# Rpi_Connections.net
KiCad netlist of a schematic drawn in Altium Designer
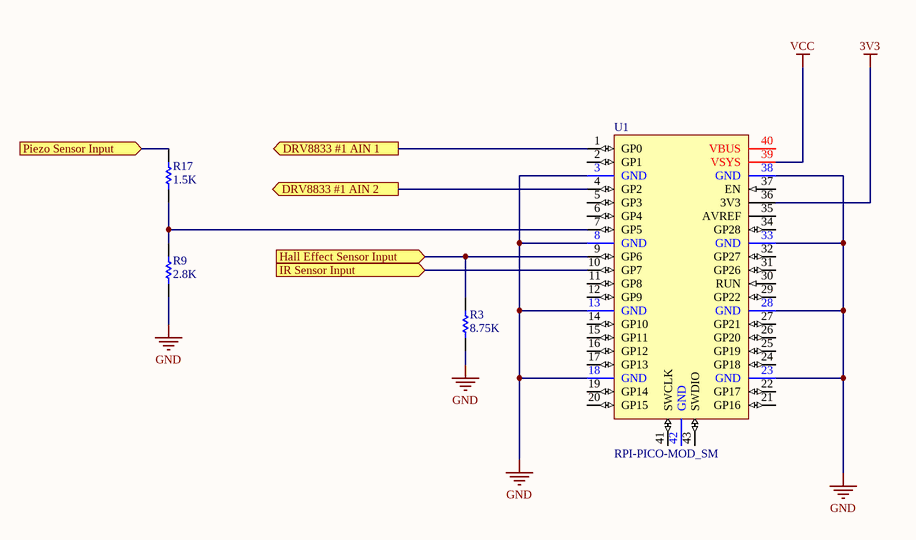
[diagram p0: Rpi Connections.SchDoc]

(export (version "E")
  (design (tool "Eeschema 10.0.6"))
  (components
    (comp (ref "R3")
      (value "8.75K")
      (description "Resistor")
      (libsource (lib "Simulation Generic Components") (part "Resistor"))
    )
    (comp (ref "R9")
      (value "2.8K")
      (description "Resistor")
      (libsource (lib "Simulation Generic Components") (part "Resistor"))
    )
    (comp (ref "R17")
      (value "1.5K")
      (description "Resistor")
      (libsource (lib "Simulation Generic Components") (part "Resistor"))
    )
    (comp (ref "U1")
      (value "RPI-PICO-MOD_SM")
      (footprint "AG.Modules:RPI-PICO-MOD")
      (description "RASPBERRY PI PICO RP2040 BOARD NO TEST PADS")
      (fields
        (field (name "MANUFACTURER") "Raspberry Pi Foundation")
        (field (name "MANUFACTURER PART NO") "SC0915")
      )
      (libsource (lib "RPi_Pico") (part "RPI-PICO-MOD_SM"))
    )
  )
  (nets
    (net (code "1") (name "/DRV8833 #1 AIN 1") (class "Default")
      (node (ref "U1") (pin "1") (pinfunction "GP0_1") (pintype "bidirectional"))
    )
    (net (code "2") (name "/DRV8833 #1 AIN 2") (class "Default")
      (node (ref "U1") (pin "4") (pinfunction "GP2_4") (pintype "bidirectional"))
    )
    (net (code "3") (name "/Hall Effect Sensor Input") (class "Default")
      (node (ref "R3") (pin "2") (pinfunction "2_2") (pintype "passive"))
      (node (ref "U1") (pin "9") (pinfunction "GP6_9") (pintype "bidirectional"))
    )
    (net (code "4") (name "/IR Sensor Input") (class "Default")
      (node (ref "U1") (pin "10") (pinfunction "GP7_10") (pintype "bidirectional"))
    )
    (net (code "5") (name "/Piezo Sensor Input") (class "Default")
      (node (ref "R17") (pin "2") (pinfunction "2_2") (pintype "passive"))
    )
    (net (code "6") (name "3V3") (class "Default")
      (node (ref "U1") (pin "36") (pinfunction "3V3_36") (pintype "power_in"))
    )
    (net (code "7") (name "GND") (class "Default")
      (node (ref "R3") (pin "1") (pinfunction "1_1") (pintype "passive"))
      (node (ref "R9") (pin "1") (pinfunction "1_1") (pintype "passive"))
      (node (ref "U1") (pin "13") (pinfunction "GND_13") (pintype "power_in"))
      (node (ref "U1") (pin "18") (pinfunction "GND_18") (pintype "power_in"))
      (node (ref "U1") (pin "23") (pinfunction "GND_23") (pintype "power_in"))
      (node (ref "U1") (pin "28") (pinfunction "GND_28") (pintype "power_in"))
      (node (ref "U1") (pin "3") (pinfunction "GND_3") (pintype "power_in"))
      (node (ref "U1") (pin "33") (pinfunction "GND_33") (pintype "power_in"))
      (node (ref "U1") (pin "38") (pinfunction "GND_38") (pintype "power_in"))
      (node (ref "U1") (pin "8") (pinfunction "GND_8") (pintype "power_in"))
    )
    (net (code "8") (name "Net-(U1-GP5)") (class "Default")
      (node (ref "R17") (pin "1") (pinfunction "1_1") (pintype "passive"))
      (node (ref "R9") (pin "2") (pinfunction "2_2") (pintype "passive"))
      (node (ref "U1") (pin "7") (pinfunction "GP5_7") (pintype "bidirectional"))
    )
    (net (code "9") (name "VCC") (class "Default")
      (node (ref "U1") (pin "39") (pinfunction "VSYS_39") (pintype "power_in"))
    )
    (net (code "10") (name "unconnected-(U1-AVREF-Pad35)") (class "Default")
      (node (ref "U1") (pin "35") (pinfunction "AVREF_35") (pintype "power_in"))
    )
    (net (code "11") (name "unconnected-(U1-EN-Pad37)") (class "Default")
      (node (ref "U1") (pin "37") (pinfunction "EN_37") (pintype "input"))
    )
    (net (code "12") (name "unconnected-(U1-GND-Pad42)") (class "Default")
      (node (ref "U1") (pin "42") (pinfunction "GND_42") (pintype "power_in"))
    )
    (net (code "13") (name "unconnected-(U1-GP1-Pad2)") (class "Default")
      (node (ref "U1") (pin "2") (pinfunction "GP1_2") (pintype "bidirectional"))
    )
    (net (code "14") (name "unconnected-(U1-GP3-Pad5)") (class "Default")
      (node (ref "U1") (pin "5") (pinfunction "GP3_5") (pintype "bidirectional"))
    )
    (net (code "15") (name "unconnected-(U1-GP4-Pad6)") (class "Default")
      (node (ref "U1") (pin "6") (pinfunction "GP4_6") (pintype "bidirectional"))
    )
    (net (code "16") (name "unconnected-(U1-GP8-Pad11)") (class "Default")
      (node (ref "U1") (pin "11") (pinfunction "GP8_11") (pintype "bidirectional"))
    )
    (net (code "17") (name "unconnected-(U1-GP9-Pad12)") (class "Default")
      (node (ref "U1") (pin "12") (pinfunction "GP9_12") (pintype "bidirectional"))
    )
    (net (code "18") (name "unconnected-(U1-GP10-Pad14)") (class "Default")
      (node (ref "U1") (pin "14") (pinfunction "GP10_14") (pintype "bidirectional"))
    )
    (net (code "19") (name "unconnected-(U1-GP11-Pad15)") (class "Default")
      (node (ref "U1") (pin "15") (pinfunction "GP11_15") (pintype "bidirectional"))
    )
    (net (code "20") (name "unconnected-(U1-GP12-Pad16)") (class "Default")
      (node (ref "U1") (pin "16") (pinfunction "GP12_16") (pintype "bidirectional"))
    )
    (net (code "21") (name "unconnected-(U1-GP13-Pad17)") (class "Default")
      (node (ref "U1") (pin "17") (pinfunction "GP13_17") (pintype "bidirectional"))
    )
    (net (code "22") (name "unconnected-(U1-GP14-Pad19)") (class "Default")
      (node (ref "U1") (pin "19") (pinfunction "GP14_19") (pintype "bidirectional"))
    )
    (net (code "23") (name "unconnected-(U1-GP15-Pad20)") (class "Default")
      (node (ref "U1") (pin "20") (pinfunction "GP15_20") (pintype "bidirectional"))
    )
    (net (code "24") (name "unconnected-(U1-GP16-Pad21)") (class "Default")
      (node (ref "U1") (pin "21") (pinfunction "GP16_21") (pintype "bidirectional"))
    )
    (net (code "25") (name "unconnected-(U1-GP17-Pad22)") (class "Default")
      (node (ref "U1") (pin "22") (pinfunction "GP17_22") (pintype "bidirectional"))
    )
    (net (code "26") (name "unconnected-(U1-GP18-Pad24)") (class "Default")
      (node (ref "U1") (pin "24") (pinfunction "GP18_24") (pintype "bidirectional"))
    )
    (net (code "27") (name "unconnected-(U1-GP19-Pad25)") (class "Default")
      (node (ref "U1") (pin "25") (pinfunction "GP19_25") (pintype "bidirectional"))
    )
    (net (code "28") (name "unconnected-(U1-GP20-Pad26)") (class "Default")
      (node (ref "U1") (pin "26") (pinfunction "GP20_26") (pintype "bidirectional"))
    )
    (net (code "29") (name "unconnected-(U1-GP21-Pad27)") (class "Default")
      (node (ref "U1") (pin "27") (pinfunction "GP21_27") (pintype "bidirectional"))
    )
    (net (code "30") (name "unconnected-(U1-GP22-Pad29)") (class "Default")
      (node (ref "U1") (pin "29") (pinfunction "GP22_29") (pintype "bidirectional"))
    )
    (net (code "31") (name "unconnected-(U1-GP26-Pad31)") (class "Default")
      (node (ref "U1") (pin "31") (pinfunction "GP26_31") (pintype "bidirectional"))
    )
    (net (code "32") (name "unconnected-(U1-GP27-Pad32)") (class "Default")
      (node (ref "U1") (pin "32") (pinfunction "GP27_32") (pintype "bidirectional"))
    )
    (net (code "33") (name "unconnected-(U1-GP28-Pad34)") (class "Default")
      (node (ref "U1") (pin "34") (pinfunction "GP28_34") (pintype "bidirectional"))
    )
    (net (code "34") (name "unconnected-(U1-RUN-Pad30)") (class "Default")
      (node (ref "U1") (pin "30") (pinfunction "RUN_30") (pintype "input"))
    )
    (net (code "35") (name "unconnected-(U1-SWCLK-Pad41)") (class "Default")
      (node (ref "U1") (pin "41") (pinfunction "SWCLK_41") (pintype "bidirectional"))
    )
    (net (code "36") (name "unconnected-(U1-SWDIO-Pad43)") (class "Default")
      (node (ref "U1") (pin "43") (pinfunction "SWDIO_43") (pintype "bidirectional"))
    )
    (net (code "37") (name "unconnected-(U1-VBUS-Pad40)") (class "Default")
      (node (ref "U1") (pin "40") (pinfunction "VBUS_40") (pintype "power_in"))
    )
  )
)
